# Sheet2.net
KiCad netlist of a schematic drawn in Altium Designer
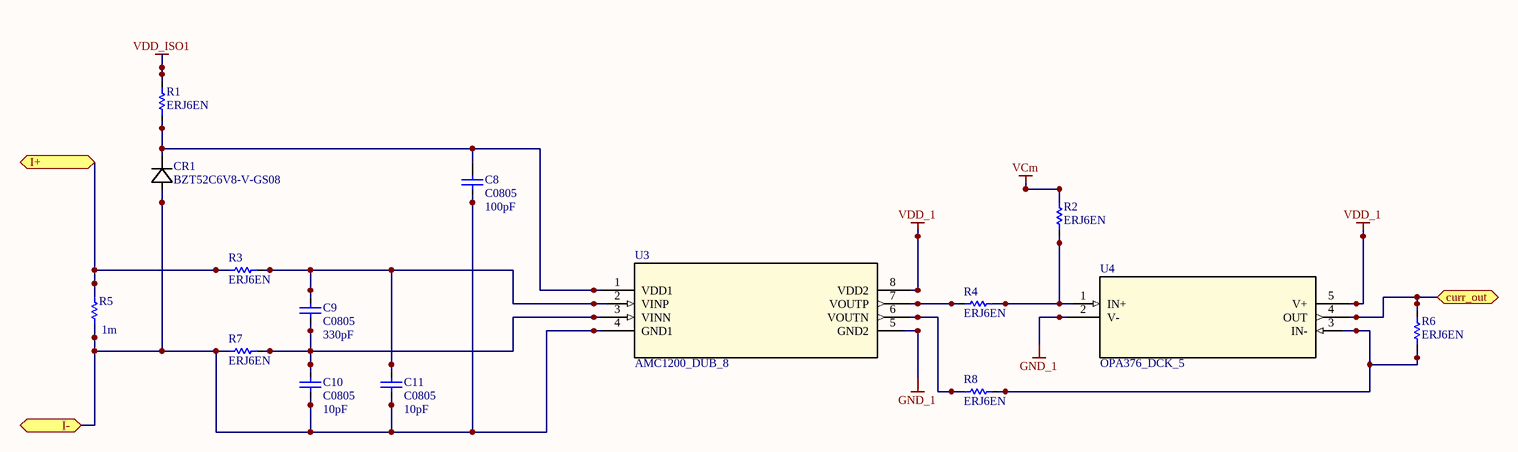
[diagram p0: Sheet2.SchDoc]

(export (version "E")
  (design (tool "Eeschema 10.0.6"))
  (components
    (comp (ref "C8")
      (value "C0805")
      (footprint "0805")
      (description "Ceramic Chip Capacitor - Standard")
      (fields (field (name "ALTIUM_VALUE") "100pF") (field (name "PUBLISHER") "Altium Limited"))
      (libsource (lib "KEMET Chip Capacitor") (part "C0805"))
    )
    (comp (ref "C9")
      (value "C0805")
      (footprint "0805")
      (description "Ceramic Chip Capacitor - Standard")
      (fields (field (name "ALTIUM_VALUE") "330pF") (field (name "PUBLISHER") "Altium Limited"))
      (libsource (lib "KEMET Chip Capacitor") (part "C0805"))
    )
    (comp (ref "C10")
      (value "C0805")
      (footprint "0805")
      (description "Ceramic Chip Capacitor - Standard")
      (fields (field (name "ALTIUM_VALUE") "10pF") (field (name "PUBLISHER") "Altium Limited"))
      (libsource (lib "KEMET Chip Capacitor") (part "C0805"))
    )
    (comp (ref "C11")
      (value "C0805")
      (footprint "0805")
      (description "Ceramic Chip Capacitor - Standard")
      (fields (field (name "ALTIUM_VALUE") "10pF") (field (name "PUBLISHER") "Altium Limited"))
      (libsource (lib "KEMET Chip Capacitor") (part "C0805"))
    )
    (comp (ref "CR1")
      (value "BZT52C6V8-V-GS08")
      (footprint "SOD123")
      (description "Imported")
      (libsource (lib "AltiumDesigner") (part "BZT52C6V8-V-GS08"))
    )
    (comp (ref "R1")
      (value "ERJ6EN")
      (footprint "6-0805")
      (description "Precision Thick Film Chip Resistor, 10 Ohm to 2.2M Ohm Range, 1% Tolerance, 0805 Size, 0.1 W")
      (fields (field (name "PUBLISHER") "Altium Limited"))
      (libsource (lib "Panasonic Resistor") (part "ERJ6EN"))
    )
    (comp (ref "R2")
      (value "ERJ6EN")
      (footprint "6-0805")
      (description "Precision Thick Film Chip Resistor, 10 Ohm to 2.2M Ohm Range, 1% Tolerance, 0805 Size, 0.1 W")
      (fields (field (name "PUBLISHER") "Altium Limited"))
      (libsource (lib "Panasonic Resistor") (part "ERJ6EN"))
    )
    (comp (ref "R3")
      (value "ERJ6EN")
      (footprint "6-0805")
      (description "Precision Thick Film Chip Resistor, 10 Ohm to 2.2M Ohm Range, 1% Tolerance, 0805 Size, 0.1 W")
      (fields (field (name "PUBLISHER") "Altium Limited"))
      (libsource (lib "Panasonic Resistor") (part "ERJ6EN"))
    )
    (comp (ref "R4")
      (value "ERJ6EN")
      (footprint "6-0805")
      (description "Precision Thick Film Chip Resistor, 10 Ohm to 2.2M Ohm Range, 1% Tolerance, 0805 Size, 0.1 W")
      (fields (field (name "PUBLISHER") "Altium Limited"))
      (libsource (lib "Panasonic Resistor") (part "ERJ6EN"))
    )
    (comp (ref "R5")
      (value "1m")
      (footprint "M1WT-2512")
      (description "Low Resistance Value Chip Resistor, 2m Ohm to 4m Ohm Range, 1% and 5% Tolerance, 2512 Size, 1 W")
      (fields (field (name "Comment") "ERJM1WT") (field (name "PUBLISHER") "Altium Limited"))
      (libsource (lib "Panasonic Resistor") (part "ERJM1WT"))
    )
    (comp (ref "R6")
      (value "ERJ6EN")
      (footprint "6-0805")
      (description "Precision Thick Film Chip Resistor, 10 Ohm to 2.2M Ohm Range, 1% Tolerance, 0805 Size, 0.1 W")
      (fields (field (name "PUBLISHER") "Altium Limited"))
      (libsource (lib "Panasonic Resistor") (part "ERJ6EN"))
    )
    (comp (ref "R7")
      (value "ERJ6EN")
      (footprint "6-0805")
      (description "Precision Thick Film Chip Resistor, 10 Ohm to 2.2M Ohm Range, 1% Tolerance, 0805 Size, 0.1 W")
      (fields (field (name "PUBLISHER") "Altium Limited"))
      (libsource (lib "Panasonic Resistor") (part "ERJ6EN"))
    )
    (comp (ref "R8")
      (value "ERJ6EN")
      (footprint "6-0805")
      (description "Precision Thick Film Chip Resistor, 10 Ohm to 2.2M Ohm Range, 1% Tolerance, 0805 Size, 0.1 W")
      (fields (field (name "PUBLISHER") "Altium Limited"))
      (libsource (lib "Panasonic Resistor") (part "ERJ6EN"))
    )
    (comp (ref "U3")
      (value "AMC1200_DUB_8")
      (footprint "DUB8")
      (description "Imported")
      (fields
        (field (name "MANUFACTURER") "Texas Instruments")
        (field (name "GENERIC_PART_NUMBER") "AMC1200")
      )
      (libsource (lib "2018-03-09_10-57-09") (part "AMC1200_DUB_8"))
    )
    (comp (ref "U4")
      (value "OPA376_DCK_5")
      (footprint "DCK5")
      (description "Imported")
      (fields (field (name "MANUFACTURER") "Texas Instruments") (field (name "GENERIC_PART_NUMBER") "OPA376"))
      (libsource (lib "2018-03-10_03-01-41") (part "OPA376_DCK_5"))
    )
  )
  (nets
    (net (code "1") (name "/I+") (class "Default")
      (node (ref "R3") (pin "1") (pinfunction "1_1") (pintype "passive"))
      (node (ref "R5") (pin "2") (pinfunction "2_2") (pintype "passive"))
    )
    (net (code "2") (name "/I-") (class "Default")
      (node (ref "C10") (pin "1") (pinfunction "1_1") (pintype "passive"))
      (node (ref "C11") (pin "1") (pinfunction "1_1") (pintype "passive"))
      (node (ref "C8") (pin "1") (pinfunction "1_1") (pintype "passive"))
      (node (ref "CR1") (pin "2") (pinfunction "2_2") (pintype "passive"))
      (node (ref "R5") (pin "1") (pinfunction "1_1") (pintype "passive"))
      (node (ref "R7") (pin "1") (pinfunction "1_1") (pintype "passive"))
      (node (ref "U3") (pin "4") (pinfunction "GND1_4") (pintype "power_in"))
    )
    (net (code "3") (name "/curr_out") (class "Default")
      (node (ref "R6") (pin "2") (pinfunction "2_2") (pintype "passive"))
      (node (ref "U4") (pin "4") (pinfunction "OUT_4") (pintype "output"))
    )
    (net (code "4") (name "GND_1") (class "Default")
      (node (ref "U3") (pin "5") (pinfunction "GND2_5") (pintype "power_in"))
      (node (ref "U4") (pin "2") (pinfunction "V-_2") (pintype "power_in"))
    )
    (net (code "5") (name "Net-(U3-VDD1)") (class "Default")
      (node (ref "C8") (pin "2") (pinfunction "2_2") (pintype "passive"))
      (node (ref "CR1") (pin "1") (pinfunction "1_1") (pintype "passive"))
      (node (ref "R1") (pin "1") (pinfunction "1_1") (pintype "passive"))
      (node (ref "U3") (pin "1") (pinfunction "VDD1_1") (pintype "power_in"))
    )
    (net (code "6") (name "Net-(U3-VINN)") (class "Default")
      (node (ref "C10") (pin "2") (pinfunction "2_2") (pintype "passive"))
      (node (ref "C9") (pin "1") (pinfunction "1_1") (pintype "passive"))
      (node (ref "R7") (pin "2") (pinfunction "2_2") (pintype "passive"))
      (node (ref "U3") (pin "3") (pinfunction "VINN_3") (pintype "input"))
    )
    (net (code "7") (name "Net-(U3-VINP)") (class "Default")
      (node (ref "C11") (pin "2") (pinfunction "2_2") (pintype "passive"))
      (node (ref "C9") (pin "2") (pinfunction "2_2") (pintype "passive"))
      (node (ref "R3") (pin "2") (pinfunction "2_2") (pintype "passive"))
      (node (ref "U3") (pin "2") (pinfunction "VINP_2") (pintype "input"))
    )
    (net (code "8") (name "Net-(U3-VOUTN)") (class "Default")
      (node (ref "R8") (pin "1") (pinfunction "1_1") (pintype "passive"))
      (node (ref "U3") (pin "6") (pinfunction "VOUTN_6") (pintype "output"))
    )
    (net (code "9") (name "Net-(U3-VOUTP)") (class "Default")
      (node (ref "R4") (pin "1") (pinfunction "1_1") (pintype "passive"))
      (node (ref "U3") (pin "7") (pinfunction "VOUTP_7") (pintype "output"))
    )
    (net (code "10") (name "Net-(U4-IN+)") (class "Default")
      (node (ref "R2") (pin "1") (pinfunction "1_1") (pintype "passive"))
      (node (ref "R4") (pin "2") (pinfunction "2_2") (pintype "passive"))
      (node (ref "U4") (pin "1") (pinfunction "IN+_1") (pintype "input"))
    )
    (net (code "11") (name "Net-(U4-IN-)") (class "Default")
      (node (ref "R6") (pin "1") (pinfunction "1_1") (pintype "passive"))
      (node (ref "R8") (pin "2") (pinfunction "2_2") (pintype "passive"))
      (node (ref "U4") (pin "3") (pinfunction "IN-_3") (pintype "input"))
    )
    (net (code "12") (name "VCm") (class "Default")
      (node (ref "R2") (pin "2") (pinfunction "2_2") (pintype "passive"))
    )
    (net (code "13") (name "VDD_1") (class "Default")
      (node (ref "U3") (pin "8") (pinfunction "VDD2_8") (pintype "power_in"))
      (node (ref "U4") (pin "5") (pinfunction "V+_5") (pintype "power_in"))
    )
    (net (code "14") (name "VDD_ISO1") (class "Default")
      (node (ref "R1") (pin "2") (pinfunction "2_2") (pintype "passive"))
    )
  )
)
